# esp8266.net
KiCad netlist of a schematic drawn in Altium Designer
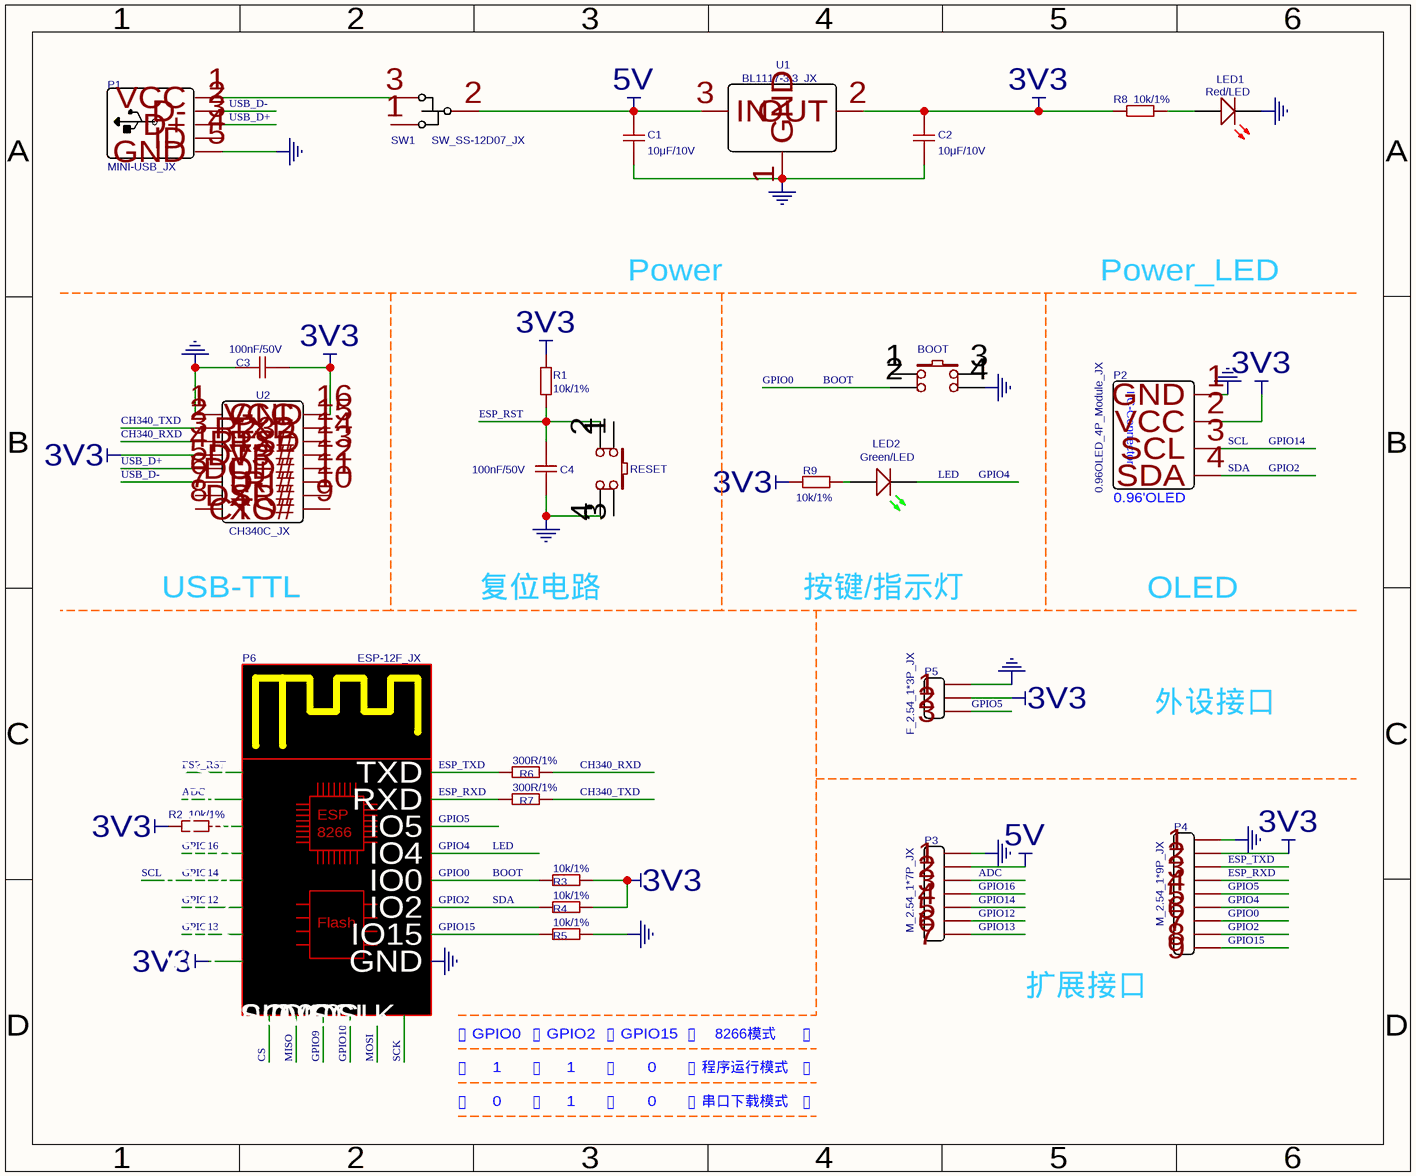
[diagram p0: esp8266.schdoc]

(export (version "E")
  (design (tool "Eeschema 10.0.6"))
  (components
    (comp (ref "BOOT") (value "SW_PUSH_JX") (libsource (lib "altium-import") (part "root_0_SW_PUSH_JX_")))
    (comp (ref "C1") (value "10μF/10V") (libsource (lib "altium-import") (part "root_1_10μF/10V_")))
    (comp (ref "C2") (value "10μF/10V") (libsource (lib "altium-import") (part "root_1_10μF/10V_")))
    (comp (ref "C3") (value "100nF/50V") (libsource (lib "altium-import") (part "root_0_100nF/50V_")))
    (comp (ref "C4") (value "100nF/50V") (libsource (lib "altium-import") (part "root_1_100nF/50V_")))
    (comp (ref "LED1") (value "Red/LED") (libsource (lib "altium-import") (part "root_0_Red/LED_")))
    (comp (ref "LED2") (value "Green/LED") (libsource (lib "altium-import") (part "root_0_Green/LED_")))
    (comp (ref "P1")
      (value "MINI-USB_JX")
      (fields (field (name "CONTRIBUTOR") "jixin-team"))
      (libsource (lib "altium-import") (part "root_0_MINI-USB_JX_"))
    )
    (comp (ref "P2")
      (value "0.96OLED_4P_Module_JX")
      (libsource (lib "altium-import") (part "root_0_0.96OLED_4P_Module_JX_"))
    )
    (comp (ref "P3")
      (value "M_2.54_1*7P_JX")
      (libsource (lib "altium-import") (part "root_0_M_2.54_1*7P_JX_"))
    )
    (comp (ref "P4")
      (value "M_2.54_1*9P_JX")
      (libsource (lib "altium-import") (part "root_0_M_2.54_1*9P_JX_"))
    )
    (comp (ref "P5")
      (value "F_2.54_1*3P_JX")
      (libsource (lib "altium-import") (part "root_0_F_2.54_1*3P_JX_"))
    )
    (comp (ref "P6") (value "ESP-12F_JX") (libsource (lib "altium-import") (part "root_0_ESP-12F_JX_")))
    (comp (ref "R1") (value "10k/1%") (libsource (lib "altium-import") (part "root_3_10k/1%_")))
    (comp (ref "R2") (value "10k/1%") (libsource (lib "altium-import") (part "root_2_10k/1%_")))
    (comp (ref "R3") (value "10k/1%") (libsource (lib "altium-import") (part "root_0_10k/1%_")))
    (comp (ref "R4") (value "10k/1%") (libsource (lib "altium-import") (part "root_2_10k/1%_")))
    (comp (ref "R5") (value "10k/1%") (libsource (lib "altium-import") (part "root_2_10k/1%_")))
    (comp (ref "R6") (value "300R/1%") (libsource (lib "altium-import") (part "root_2_300R/1%_")))
    (comp (ref "R7") (value "300R/1%") (libsource (lib "altium-import") (part "root_2_300R/1%_")))
    (comp (ref "R8") (value "10k/1%") (libsource (lib "altium-import") (part "root_2_10k/1%_")))
    (comp (ref "R9") (value "10k/1%") (libsource (lib "altium-import") (part "root_2_10k/1%_")))
    (comp (ref "RESET") (value "SW_PUSH_JX") (libsource (lib "altium-import") (part "root_3_SW_PUSH_JX_")))
    (comp (ref "SW1")
      (value "SW_SS-12D07_JX")
      (fields (field (name "CONTRIBUTOR") "jixin-team"))
      (libsource (lib "altium-import") (part "root_2_SW_SS-12D07_JX_"))
    )
    (comp (ref "U1")
      (value "BL1117-3.3_JX")
      (fields (field (name "CONTRIBUTOR") "jixin002"))
      (libsource (lib "altium-import") (part "root_0_BL1117-3.3_JX_"))
    )
    (comp (ref "U2") (value "CH340C_JX") (libsource (lib "altium-import") (part "root_0_CH340C_JX_")))
  )
  (nets
    (net (code "1") (name "/ADC") (class "Default")
      (node (ref "P3") (pin "3") (pinfunction "3_3") (pintype "passive"))
      (node (ref "P6") (pin "2") (pinfunction "ADC_2") (pintype "passive"))
    )
    (net (code "2") (name "/BOOT") (class "Default")
      (node (ref "BOOT") (pin "2") (pinfunction "2_2") (pintype "passive"))
      (node (ref "P4") (pin "7") (pinfunction "7_7") (pintype "passive"))
      (node (ref "P6") (pin "18") (pinfunction "IO0_18") (pintype "passive"))
      (node (ref "R3") (pin "1") (pinfunction "1_1") (pintype "passive"))
    )
    (net (code "3") (name "/CH340_RXD") (class "Default")
      (node (ref "R6") (pin "1") (pinfunction "1_1") (pintype "passive"))
      (node (ref "U2") (pin "3") (pinfunction "RXD_3") (pintype "passive"))
    )
    (net (code "4") (name "/CH340_TXD") (class "Default")
      (node (ref "R7") (pin "1") (pinfunction "1_1") (pintype "passive"))
      (node (ref "U2") (pin "2") (pinfunction "TXD_2") (pintype "passive"))
    )
    (net (code "5") (name "/CS") (class "Default")
      (node (ref "P6") (pin "9") (pinfunction "CS0_9") (pintype "passive"))
    )
    (net (code "6") (name "/ESP_RST") (class "Default")
      (node (ref "C4") (pin "2") (pinfunction "2_2") (pintype "passive"))
      (node (ref "P6") (pin "1") (pinfunction "RST_1") (pintype "passive"))
      (node (ref "R1") (pin "2") (pinfunction "2_2") (pintype "passive"))
      (node (ref "RESET") (pin "2") (pinfunction "2_2") (pintype "passive"))
    )
    (net (code "7") (name "/ESP_RXD") (class "Default")
      (node (ref "P4") (pin "4") (pinfunction "4_4") (pintype "passive"))
      (node (ref "P6") (pin "21") (pinfunction "RXD_21") (pintype "passive"))
      (node (ref "R7") (pin "2") (pinfunction "2_2") (pintype "passive"))
    )
    (net (code "8") (name "/ESP_TXD") (class "Default")
      (node (ref "P4") (pin "3") (pinfunction "3_3") (pintype "passive"))
      (node (ref "P6") (pin "22") (pinfunction "TXD_22") (pintype "passive"))
      (node (ref "R6") (pin "2") (pinfunction "2_2") (pintype "passive"))
    )
    (net (code "9") (name "/GPIO2") (class "Default")
      (node (ref "P2") (pin "4") (pinfunction "SDA_4") (pintype "passive"))
      (node (ref "P4") (pin "8") (pinfunction "8_8") (pintype "passive"))
      (node (ref "P6") (pin "17") (pinfunction "IO2_17") (pintype "passive"))
      (node (ref "R4") (pin "2") (pinfunction "2_2") (pintype "passive"))
    )
    (net (code "10") (name "/GPIO4") (class "Default")
      (node (ref "LED2") (pin "2") (pinfunction "C_2") (pintype "passive"))
      (node (ref "P4") (pin "6") (pinfunction "6_6") (pintype "passive"))
      (node (ref "P6") (pin "19") (pinfunction "IO4_19") (pintype "passive"))
    )
    (net (code "11") (name "/GPIO5") (class "Default")
      (node (ref "P4") (pin "5") (pinfunction "5_5") (pintype "passive"))
      (node (ref "P5") (pin "3") (pinfunction "3_3") (pintype "passive"))
      (node (ref "P6") (pin "20") (pinfunction "IO5_20") (pintype "passive"))
    )
    (net (code "12") (name "/GPIO9") (class "Default")
      (node (ref "P6") (pin "11") (pinfunction "IO9_11") (pintype "passive"))
    )
    (net (code "13") (name "/GPIO10") (class "Default")
      (node (ref "P6") (pin "12") (pinfunction "IO10_12") (pintype "passive"))
    )
    (net (code "14") (name "/GPIO12") (class "Default")
      (node (ref "P3") (pin "6") (pinfunction "6_6") (pintype "passive"))
      (node (ref "P6") (pin "6") (pinfunction "IO12_6") (pintype "passive"))
    )
    (net (code "15") (name "/GPIO13") (class "Default")
      (node (ref "P3") (pin "7") (pinfunction "7_7") (pintype "passive"))
      (node (ref "P6") (pin "7") (pinfunction "IO13_7") (pintype "passive"))
    )
    (net (code "16") (name "/GPIO14") (class "Default")
      (node (ref "P2") (pin "3") (pinfunction "SCL_3") (pintype "passive"))
      (node (ref "P3") (pin "5") (pinfunction "5_5") (pintype "passive"))
      (node (ref "P6") (pin "5") (pinfunction "IO14_5") (pintype "passive"))
    )
    (net (code "17") (name "/GPIO15") (class "Default")
      (node (ref "P4") (pin "9") (pinfunction "9_9") (pintype "passive"))
      (node (ref "P6") (pin "16") (pinfunction "IO15_16") (pintype "passive"))
      (node (ref "R5") (pin "2") (pinfunction "2_2") (pintype "passive"))
    )
    (net (code "18") (name "/GPIO16") (class "Default")
      (node (ref "P3") (pin "4") (pinfunction "4_4") (pintype "passive"))
      (node (ref "P6") (pin "4") (pinfunction "IO16_4") (pintype "passive"))
    )
    (net (code "19") (name "/MISO") (class "Default")
      (node (ref "P6") (pin "10") (pinfunction "MISO_10") (pintype "passive"))
    )
    (net (code "20") (name "/MOSI") (class "Default")
      (node (ref "P6") (pin "13") (pinfunction "MOSI_13") (pintype "passive"))
    )
    (net (code "21") (name "/SCK") (class "Default")
      (node (ref "P6") (pin "14") (pinfunction "SCLK_14") (pintype "passive"))
    )
    (net (code "22") (name "/USB_D+") (class "Default")
      (node (ref "P1") (pin "3") (pinfunction "D+_3") (pintype "passive"))
      (node (ref "U2") (pin "5") (pinfunction "D+_5") (pintype "passive"))
    )
    (net (code "23") (name "/USB_D-") (class "Default")
      (node (ref "P1") (pin "2") (pinfunction "D-_2") (pintype "passive"))
      (node (ref "U2") (pin "6") (pinfunction "D-_6") (pintype "passive"))
    )
    (net (code "24") (name "3V3") (class "Default")
      (node (ref "C2") (pin "2") (pinfunction "2_2") (pintype "passive"))
      (node (ref "C3") (pin "2") (pinfunction "2_2") (pintype "passive"))
      (node (ref "P2") (pin "2") (pinfunction "VCC_2") (pintype "passive"))
      (node (ref "P4") (pin "2") (pinfunction "2_2") (pintype "passive"))
      (node (ref "P5") (pin "2") (pinfunction "2_2") (pintype "passive"))
      (node (ref "P6") (pin "8") (pinfunction "VCC_8") (pintype "passive"))
      (node (ref "R1") (pin "1") (pinfunction "1_1") (pintype "passive"))
      (node (ref "R2") (pin "2") (pinfunction "2_2") (pintype "passive"))
      (node (ref "R3") (pin "2") (pinfunction "2_2") (pintype "passive"))
      (node (ref "R4") (pin "1") (pinfunction "1_1") (pintype "passive"))
      (node (ref "R8") (pin "2") (pinfunction "2_2") (pintype "passive"))
      (node (ref "R9") (pin "2") (pinfunction "2_2") (pintype "passive"))
      (node (ref "U1") (pin "2") (pinfunction "OUT_2") (pintype "passive"))
      (node (ref "U2") (pin "16") (pinfunction "VCC_16") (pintype "passive"))
      (node (ref "U2") (pin "4") (pinfunction "V3_4") (pintype "passive"))
    )
    (net (code "25") (name "5V") (class "Default")
      (node (ref "C1") (pin "2") (pinfunction "2_2") (pintype "passive"))
      (node (ref "P3") (pin "2") (pinfunction "2_2") (pintype "passive"))
      (node (ref "SW1") (pin "2") (pinfunction "2_2") (pintype "passive"))
      (node (ref "U1") (pin "3") (pinfunction "IN_3") (pintype "passive"))
    )
    (net (code "26") (name "GND") (class "Default")
      (node (ref "BOOT") (pin "4") (pinfunction "4_4") (pintype "passive"))
      (node (ref "C1") (pin "1") (pinfunction "1_1") (pintype "passive"))
      (node (ref "C2") (pin "1") (pinfunction "1_1") (pintype "passive"))
      (node (ref "C3") (pin "1") (pinfunction "1_1") (pintype "passive"))
      (node (ref "C4") (pin "1") (pinfunction "1_1") (pintype "passive"))
      (node (ref "LED1") (pin "2") (pinfunction "C_2") (pintype "passive"))
      (node (ref "P1") (pin "5") (pinfunction "GND_5") (pintype "passive"))
      (node (ref "P2") (pin "1") (pinfunction "GND_1") (pintype "passive"))
      (node (ref "P3") (pin "1") (pinfunction "1_1") (pintype "passive"))
      (node (ref "P4") (pin "1") (pinfunction "1_1") (pintype "passive"))
      (node (ref "P5") (pin "1") (pinfunction "1_1") (pintype "passive"))
      (node (ref "P6") (pin "15") (pinfunction "GND_15") (pintype "passive"))
      (node (ref "R5") (pin "1") (pinfunction "1_1") (pintype "passive"))
      (node (ref "RESET") (pin "4") (pinfunction "4_4") (pintype "passive"))
      (node (ref "U1") (pin "1") (pinfunction "GND_1") (pintype "passive"))
      (node (ref "U2") (pin "1") (pinfunction "GND_1") (pintype "passive"))
    )
    (net (code "27") (name "Net-(LED1-A)") (class "Default")
      (node (ref "LED1") (pin "1") (pinfunction "A_1") (pintype "passive"))
      (node (ref "R8") (pin "1") (pinfunction "1_1") (pintype "passive"))
    )
    (net (code "28") (name "Net-(LED2-A)") (class "Default")
      (node (ref "LED2") (pin "1") (pinfunction "A_1") (pintype "passive"))
      (node (ref "R9") (pin "1") (pinfunction "1_1") (pintype "passive"))
    )
    (net (code "29") (name "Net-(P1-VCC)") (class "Default")
      (node (ref "P1") (pin "1") (pinfunction "VCC_1") (pintype "passive"))
      (node (ref "SW1") (pin "3") (pinfunction "3_3") (pintype "passive"))
    )
    (net (code "30") (name "Net-(P6-EN)") (class "Default")
      (node (ref "P6") (pin "3") (pinfunction "EN_3") (pintype "passive"))
      (node (ref "R2") (pin "1") (pinfunction "1_1") (pintype "passive"))
    )
    (net (code "31") (name "unconnected-(BOOT-Pad1)") (class "Default")
      (node (ref "BOOT") (pin "1") (pinfunction "1_1") (pintype "passive"))
    )
    (net (code "32") (name "unconnected-(BOOT-Pad3)") (class "Default")
      (node (ref "BOOT") (pin "3") (pinfunction "3_3") (pintype "passive"))
    )
    (net (code "33") (name "unconnected-(P1-ID-Pad4)") (class "Default")
      (node (ref "P1") (pin "4") (pinfunction "ID_4") (pintype "passive"))
    )
    (net (code "34") (name "unconnected-(RESET-Pad1)") (class "Default")
      (node (ref "RESET") (pin "1") (pinfunction "1_1") (pintype "passive"))
    )
    (net (code "35") (name "unconnected-(RESET-Pad3)") (class "Default")
      (node (ref "RESET") (pin "3") (pinfunction "3_3") (pintype "passive"))
    )
    (net (code "36") (name "unconnected-(SW1-Pad1)") (class "Default")
      (node (ref "SW1") (pin "1") (pinfunction "1_1") (pintype "passive"))
    )
    (net (code "37") (name "unconnected-(U2-CTS#-Pad9)") (class "Default")
      (node (ref "U2") (pin "9") (pinfunction "CTS#_9") (pintype "passive"))
    )
    (net (code "38") (name "unconnected-(U2-DCD#-Pad12)") (class "Default")
      (node (ref "U2") (pin "12") (pinfunction "DCD#_12") (pintype "passive"))
    )
    (net (code "39") (name "unconnected-(U2-DSR#-Pad10)") (class "Default")
      (node (ref "U2") (pin "10") (pinfunction "DSR#_10") (pintype "passive"))
    )
    (net (code "40") (name "unconnected-(U2-DTR#-Pad13)") (class "Default")
      (node (ref "U2") (pin "13") (pinfunction "DTR#_13") (pintype "passive"))
    )
    (net (code "41") (name "unconnected-(U2-R232-Pad15)") (class "Default")
      (node (ref "U2") (pin "15") (pinfunction "R232_15") (pintype "passive"))
    )
    (net (code "42") (name "unconnected-(U2-RI#-Pad11)") (class "Default")
      (node (ref "U2") (pin "11") (pinfunction "RI#_11") (pintype "passive"))
    )
    (net (code "43") (name "unconnected-(U2-RTS#-Pad14)") (class "Default")
      (node (ref "U2") (pin "14") (pinfunction "RTS#_14") (pintype "passive"))
    )
    (net (code "44") (name "unconnected-(U2-XI-Pad7)") (class "Default")
      (node (ref "U2") (pin "7") (pinfunction "XI_7") (pintype "passive"))
    )
    (net (code "45") (name "unconnected-(U2-XO-Pad8)") (class "Default")
      (node (ref "U2") (pin "8") (pinfunction "XO_8") (pintype "passive"))
    )
  )
)
